# CustomPower.net
KiCad netlist of a schematic drawn in EAGLE
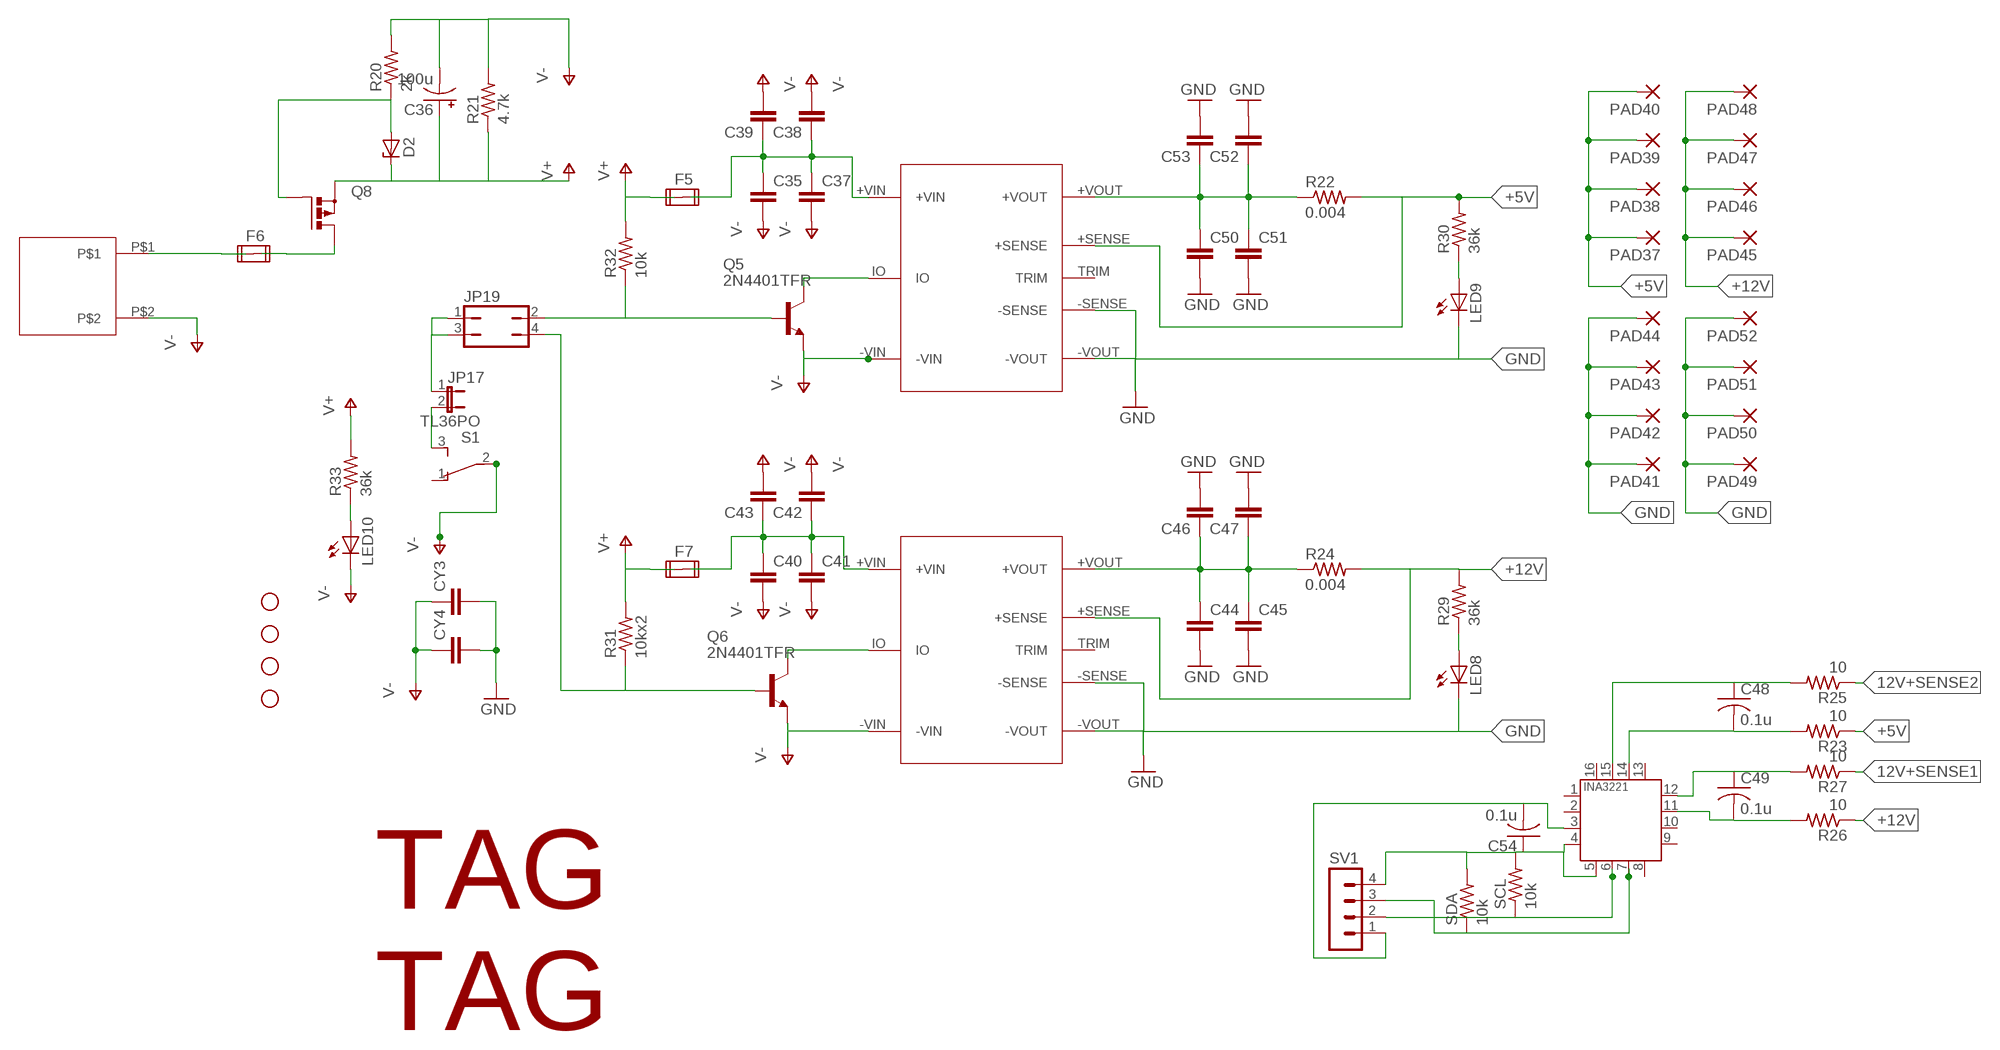
[diagram p0: schematic, sheet 1]

(export (version "E")
  (design (tool "Eeschema 10.0.6"))
  (components
    (comp (ref "C35")
      (value "C-EU050-035X075")
      (footprint "eagle-import:C050-035X075")
      (libsource (lib "eagle-import") (part "C-EU050-035X075"))
    )
    (comp (ref "C36")
      (value "100u")
      (footprint "eagle-import:E3,5-8")
      (libsource (lib "eagle-import") (part "CPOL-USE3.5-8"))
    )
    (comp (ref "C37")
      (value "C-EU050-035X075")
      (footprint "eagle-import:C050-035X075")
      (libsource (lib "eagle-import") (part "C-EU050-035X075"))
    )
    (comp (ref "C38")
      (value "C-EU050-035X075")
      (footprint "eagle-import:C050-035X075")
      (libsource (lib "eagle-import") (part "C-EU050-035X075"))
    )
    (comp (ref "C39")
      (value "C-EU050-035X075")
      (footprint "eagle-import:C050-035X075")
      (libsource (lib "eagle-import") (part "C-EU050-035X075"))
    )
    (comp (ref "C40")
      (value "C-EU050-035X075")
      (footprint "eagle-import:C050-035X075")
      (libsource (lib "eagle-import") (part "C-EU050-035X075"))
    )
    (comp (ref "C41")
      (value "C-EU050-035X075")
      (footprint "eagle-import:C050-035X075")
      (libsource (lib "eagle-import") (part "C-EU050-035X075"))
    )
    (comp (ref "C42")
      (value "C-EU050-035X075")
      (footprint "eagle-import:C050-035X075")
      (libsource (lib "eagle-import") (part "C-EU050-035X075"))
    )
    (comp (ref "C43")
      (value "C-EU050-035X075")
      (footprint "eagle-import:C050-035X075")
      (libsource (lib "eagle-import") (part "C-EU050-035X075"))
    )
    (comp (ref "C44")
      (value "C-EU025-040X050")
      (footprint "eagle-import:C025-040X050")
      (libsource (lib "eagle-import") (part "C-EU025-040X050"))
    )
    (comp (ref "C45")
      (value "C-EU025-040X050")
      (footprint "eagle-import:C025-040X050")
      (libsource (lib "eagle-import") (part "C-EU025-040X050"))
    )
    (comp (ref "C46")
      (value "C-EU025-040X050")
      (footprint "eagle-import:C025-040X050")
      (libsource (lib "eagle-import") (part "C-EU025-040X050"))
    )
    (comp (ref "C47")
      (value "C-EU025-040X050")
      (footprint "eagle-import:C025-040X050")
      (libsource (lib "eagle-import") (part "C-EU025-040X050"))
    )
    (comp (ref "C48")
      (value "0.1u")
      (footprint "eagle-import:C0805K")
      (libsource (lib "eagle-import") (part "C-USC0805K"))
    )
    (comp (ref "C49")
      (value "0.1u")
      (footprint "eagle-import:C0805K")
      (libsource (lib "eagle-import") (part "C-USC0805K"))
    )
    (comp (ref "C50")
      (value "C-EU025-040X050")
      (footprint "eagle-import:C025-040X050")
      (libsource (lib "eagle-import") (part "C-EU025-040X050"))
    )
    (comp (ref "C51")
      (value "C-EU025-040X050")
      (footprint "eagle-import:C025-040X050")
      (libsource (lib "eagle-import") (part "C-EU025-040X050"))
    )
    (comp (ref "C52")
      (value "C-EU025-040X050")
      (footprint "eagle-import:C025-040X050")
      (libsource (lib "eagle-import") (part "C-EU025-040X050"))
    )
    (comp (ref "C53")
      (value "C-EU025-040X050")
      (footprint "eagle-import:C025-040X050")
      (libsource (lib "eagle-import") (part "C-EU025-040X050"))
    )
    (comp (ref "C54")
      (value "0.1u")
      (footprint "eagle-import:C0805K")
      (libsource (lib "eagle-import") (part "C-USC0805K"))
    )
    (comp (ref "CY3")
      (value "CYYC7B5")
      (footprint "eagle-import:YC7B5")
      (libsource (lib "eagle-import") (part "CYYC7B5"))
    )
    (comp (ref "CY4")
      (value "CYYC7B5")
      (footprint "eagle-import:YC7B5")
      (libsource (lib "eagle-import") (part "CYYC7B5"))
    )
    (comp (ref "D2")
      (value "BZV10")
      (footprint "eagle-import:DO34Z7")
      (libsource (lib "eagle-import") (part "BZV10"))
    )
    (comp (ref "F5")
      (value "FUSE2P")
      (footprint "eagle-import:FUSE1")
      (libsource (lib "eagle-import") (part "FUSE2P"))
    )
    (comp (ref "F6")
      (value "FUSE2P")
      (footprint "eagle-import:FUSE1")
      (fields (field (name "SPICEPREFIX") "E"))
      (libsource (lib "eagle-import") (part "FUSE2P"))
    )
    (comp (ref "F7")
      (value "FUSE2P")
      (footprint "eagle-import:FUSE1")
      (libsource (lib "eagle-import") (part "FUSE2P"))
    )
    (comp (ref "JP3")
      (value "STAND-OFF")
      (footprint "eagle-import:STAND-OFF")
      (libsource (lib "eagle-import") (part "STAND-OFF"))
    )
    (comp (ref "JP4")
      (value "STAND-OFF")
      (footprint "eagle-import:STAND-OFF")
      (libsource (lib "eagle-import") (part "STAND-OFF"))
    )
    (comp (ref "JP5")
      (value "STAND-OFF")
      (footprint "eagle-import:STAND-OFF")
      (libsource (lib "eagle-import") (part "STAND-OFF"))
    )
    (comp (ref "JP6")
      (value "STAND-OFF")
      (footprint "eagle-import:STAND-OFF")
      (libsource (lib "eagle-import") (part "STAND-OFF"))
    )
    (comp (ref "JP17")
      (value "JP1E")
      (footprint "eagle-import:JP1")
      (libsource (lib "eagle-import") (part "JP1E"))
    )
    (comp (ref "JP19")
      (value "JP2Q")
      (footprint "eagle-import:JP2Q")
      (libsource (lib "eagle-import") (part "JP2Q"))
    )
    (comp (ref "LED8")
      (value "LEDSMT1206")
      (footprint "eagle-import:1206")
      (libsource (lib "eagle-import") (part "LEDSMT1206"))
    )
    (comp (ref "LED9")
      (value "LEDSMT1206")
      (footprint "eagle-import:1206")
      (libsource (lib "eagle-import") (part "LEDSMT1206"))
    )
    (comp (ref "LED10")
      (value "LEDSMT1206")
      (footprint "eagle-import:1206")
      (libsource (lib "eagle-import") (part "LEDSMT1206"))
    )
    (comp (ref "PAD37")
      (value "WIREPAD3,17/1,3")
      (footprint "eagle-import:3,17_1,3")
      (libsource (lib "eagle-import") (part "WIREPAD3,17/1,3"))
    )
    (comp (ref "PAD38")
      (value "WIREPAD3,17/1,3")
      (footprint "eagle-import:3,17_1,3")
      (libsource (lib "eagle-import") (part "WIREPAD3,17/1,3"))
    )
    (comp (ref "PAD39")
      (value "WIREPAD3,17/1,3")
      (footprint "eagle-import:3,17_1,3")
      (libsource (lib "eagle-import") (part "WIREPAD3,17/1,3"))
    )
    (comp (ref "PAD40")
      (value "WIREPAD3,17/1,3")
      (footprint "eagle-import:3,17_1,3")
      (libsource (lib "eagle-import") (part "WIREPAD3,17/1,3"))
    )
    (comp (ref "PAD41")
      (value "WIREPAD3,17/1,3")
      (footprint "eagle-import:3,17_1,3")
      (libsource (lib "eagle-import") (part "WIREPAD3,17/1,3"))
    )
    (comp (ref "PAD42")
      (value "WIREPAD3,17/1,3")
      (footprint "eagle-import:3,17_1,3")
      (libsource (lib "eagle-import") (part "WIREPAD3,17/1,3"))
    )
    (comp (ref "PAD43")
      (value "WIREPAD3,17/1,3")
      (footprint "eagle-import:3,17_1,3")
      (libsource (lib "eagle-import") (part "WIREPAD3,17/1,3"))
    )
    (comp (ref "PAD44")
      (value "WIREPAD3,17/1,3")
      (footprint "eagle-import:3,17_1,3")
      (libsource (lib "eagle-import") (part "WIREPAD3,17/1,3"))
    )
    (comp (ref "PAD45")
      (value "WIREPAD3,17/1,3")
      (footprint "eagle-import:3,17_1,3")
      (libsource (lib "eagle-import") (part "WIREPAD3,17/1,3"))
    )
    (comp (ref "PAD46")
      (value "WIREPAD3,17/1,3")
      (footprint "eagle-import:3,17_1,3")
      (libsource (lib "eagle-import") (part "WIREPAD3,17/1,3"))
    )
    (comp (ref "PAD47")
      (value "WIREPAD3,17/1,3")
      (footprint "eagle-import:3,17_1,3")
      (libsource (lib "eagle-import") (part "WIREPAD3,17/1,3"))
    )
    (comp (ref "PAD48")
      (value "WIREPAD3,17/1,3")
      (footprint "eagle-import:3,17_1,3")
      (libsource (lib "eagle-import") (part "WIREPAD3,17/1,3"))
    )
    (comp (ref "PAD49")
      (value "WIREPAD3,17/1,3")
      (footprint "eagle-import:3,17_1,3")
      (libsource (lib "eagle-import") (part "WIREPAD3,17/1,3"))
    )
    (comp (ref "PAD50")
      (value "WIREPAD3,17/1,3")
      (footprint "eagle-import:3,17_1,3")
      (libsource (lib "eagle-import") (part "WIREPAD3,17/1,3"))
    )
    (comp (ref "PAD51")
      (value "WIREPAD3,17/1,3")
      (footprint "eagle-import:3,17_1,3")
      (libsource (lib "eagle-import") (part "WIREPAD3,17/1,3"))
    )
    (comp (ref "PAD52")
      (value "WIREPAD3,17/1,3")
      (footprint "eagle-import:3,17_1,3")
      (libsource (lib "eagle-import") (part "WIREPAD3,17/1,3"))
    )
    (comp (ref "Q5")
      (value "2N4401TFR")
      (footprint "eagle-import:TO92-EBC")
      (libsource (lib "eagle-import") (part "2N4401TFR"))
    )
    (comp (ref "Q6")
      (value "2N4401TFR")
      (footprint "eagle-import:TO92-EBC")
      (libsource (lib "eagle-import") (part "2N4401TFR"))
    )
    (comp (ref "Q8")
      (value "PMOSFET_PTO220BV")
      (footprint "eagle-import:TO220BV")
      (libsource (lib "eagle-import") (part "PMOSFET_PTO220BV"))
    )
    (comp (ref "R20")
      (value "2k")
      (footprint "eagle-import:0204_7")
      (libsource (lib "eagle-import") (part "resistor_348_R-US_0204/7"))
    )
    (comp (ref "R21")
      (value "4.7k")
      (footprint "eagle-import:0204_7")
      (libsource (lib "eagle-import") (part "resistor_348_R-US_0204/7"))
    )
    (comp (ref "R22")
      (value "0.004")
      (footprint "eagle-import:0617_22")
      (libsource (lib "eagle-import") (part "R-US_0617/22"))
    )
    (comp (ref "R23")
      (value "10")
      (footprint "eagle-import:R0805")
      (libsource (lib "eagle-import") (part "resistor_348_R-US_R0805"))
    )
    (comp (ref "R24")
      (value "0.004")
      (footprint "eagle-import:0617_22")
      (libsource (lib "eagle-import") (part "R-US_0617/22"))
    )
    (comp (ref "R25")
      (value "10")
      (footprint "eagle-import:R0805")
      (libsource (lib "eagle-import") (part "resistor_348_R-US_R0805"))
    )
    (comp (ref "R26")
      (value "10")
      (footprint "eagle-import:R0805")
      (libsource (lib "eagle-import") (part "resistor_348_R-US_R0805"))
    )
    (comp (ref "R27")
      (value "10")
      (footprint "eagle-import:R0805")
      (libsource (lib "eagle-import") (part "resistor_348_R-US_R0805"))
    )
    (comp (ref "R29")
      (value "36k")
      (footprint "eagle-import:R0805")
      (libsource (lib "eagle-import") (part "resistor_348_R-US_R0805"))
    )
    (comp (ref "R30")
      (value "36k")
      (footprint "eagle-import:R0805")
      (libsource (lib "eagle-import") (part "resistor_348_R-US_R0805"))
    )
    (comp (ref "R31")
      (value "10kx2")
      (footprint "eagle-import:R0805")
      (libsource (lib "eagle-import") (part "resistor_348_R-US_R0805"))
    )
    (comp (ref "R32")
      (value "10k")
      (footprint "eagle-import:R0805")
      (libsource (lib "eagle-import") (part "resistor_348_R-US_R0805"))
    )
    (comp (ref "R33")
      (value "36k")
      (footprint "eagle-import:R0805")
      (libsource (lib "eagle-import") (part "resistor_348_R-US_R0805"))
    )
    (comp (ref "S1")
      (value "TL36PO")
      (footprint "eagle-import:TL3XPO")
      (libsource (lib "eagle-import") (part "TL36PO"))
    )
    (comp (ref "SCL")
      (value "10k")
      (footprint "eagle-import:R0805")
      (libsource (lib "eagle-import") (part "resistor_348_R-US_R0805"))
    )
    (comp (ref "SDA")
      (value "10k")
      (footprint "eagle-import:R0805")
      (libsource (lib "eagle-import") (part "resistor_348_R-US_R0805"))
    )
    (comp (ref "SV1")
      (value "MA04-1")
      (footprint "eagle-import:MA04-1")
      (libsource (lib "eagle-import") (part "MA04-1"))
    )
    (comp (ref "U$1")
      (value "MURATA_BRICK")
      (footprint "eagle-import:MURATA_BRICK")
      (libsource (lib "eagle-import") (part "MURATA_BRICK"))
    )
    (comp (ref "U$2")
      (value "MURATA_BRICK")
      (footprint "eagle-import:MURATA_BRICK")
      (libsource (lib "eagle-import") (part "MURATA_BRICK"))
    )
    (comp (ref "U$3")
      (value "TERM_POWER")
      (footprint "eagle-import:TERM_BLOCK_POWER")
      (libsource (lib "eagle-import") (part "TERM_POWER"))
    )
    (comp (ref "U$4")
      (value "TAG")
      (footprint "eagle-import:TAG")
      (libsource (lib "eagle-import") (part "TAG"))
    )
    (comp (ref "U$5")
      (value "TAG")
      (footprint "eagle-import:TAG")
      (libsource (lib "eagle-import") (part "TAG"))
    )
    (comp (ref "U3")
      (value "INA3221.")
      (footprint "eagle-import:HVQFN16_4X4")
      (libsource (lib "eagle-import") (part "INA3221."))
    )
  )
  (nets
    (net (code "1") (name "+5V") (class "Default")
      (node (ref "PAD37") (pin "1") (pinfunction "P_1") (pintype "passive"))
      (node (ref "PAD38") (pin "1") (pinfunction "P_1") (pintype "passive"))
      (node (ref "PAD39") (pin "1") (pinfunction "P_1") (pintype "passive"))
      (node (ref "PAD40") (pin "1") (pinfunction "P_1") (pintype "passive"))
      (node (ref "R22") (pin "2") (pinfunction "2_2") (pintype "passive"))
      (node (ref "R23") (pin "1") (pinfunction "1_1") (pintype "passive"))
      (node (ref "R30") (pin "2") (pinfunction "2_2") (pintype "passive"))
      (node (ref "U$1") (pin "+SENSE") (pinfunction "+SENSE_+SENSE") (pintype "bidirectional"))
    )
    (net (code "2") (name "+12V") (class "Default")
      (node (ref "PAD45") (pin "1") (pinfunction "P_1") (pintype "passive"))
      (node (ref "PAD46") (pin "1") (pinfunction "P_1") (pintype "passive"))
      (node (ref "PAD47") (pin "1") (pinfunction "P_1") (pintype "passive"))
      (node (ref "PAD48") (pin "1") (pinfunction "P_1") (pintype "passive"))
      (node (ref "R24") (pin "2") (pinfunction "2_2") (pintype "passive"))
      (node (ref "R26") (pin "1") (pinfunction "1_1") (pintype "passive"))
      (node (ref "R29") (pin "2") (pinfunction "2_2") (pintype "passive"))
      (node (ref "U$2") (pin "+SENSE") (pinfunction "+SENSE_+SENSE") (pintype "bidirectional"))
    )
    (net (code "3") (name "12V+SENSE1") (class "Default")
      (node (ref "C44") (pin "1") (pinfunction "1_1") (pintype "passive"))
      (node (ref "C45") (pin "1") (pinfunction "1_1") (pintype "passive"))
      (node (ref "C46") (pin "1") (pinfunction "1_1") (pintype "passive"))
      (node (ref "C47") (pin "1") (pinfunction "1_1") (pintype "passive"))
      (node (ref "R24") (pin "1") (pinfunction "1_1") (pintype "passive"))
      (node (ref "R27") (pin "1") (pinfunction "1_1") (pintype "passive"))
      (node (ref "U$2") (pin "+VOUT") (pinfunction "+VOUT_+VOUT") (pintype "bidirectional"))
    )
    (net (code "4") (name "12V+SENSE2") (class "Default")
      (node (ref "C50") (pin "1") (pinfunction "1_1") (pintype "passive"))
      (node (ref "C51") (pin "1") (pinfunction "1_1") (pintype "passive"))
      (node (ref "C52") (pin "1") (pinfunction "1_1") (pintype "passive"))
      (node (ref "C53") (pin "1") (pinfunction "1_1") (pintype "passive"))
      (node (ref "R22") (pin "1") (pinfunction "1_1") (pintype "passive"))
      (node (ref "R25") (pin "1") (pinfunction "1_1") (pintype "passive"))
      (node (ref "U$1") (pin "+VOUT") (pinfunction "+VOUT_+VOUT") (pintype "bidirectional"))
    )
    (net (code "5") (name "GND") (class "Default")
      (node (ref "C44") (pin "2") (pinfunction "2_2") (pintype "passive"))
      (node (ref "C45") (pin "2") (pinfunction "2_2") (pintype "passive"))
      (node (ref "C46") (pin "2") (pinfunction "2_2") (pintype "passive"))
      (node (ref "C47") (pin "2") (pinfunction "2_2") (pintype "passive"))
      (node (ref "C50") (pin "2") (pinfunction "2_2") (pintype "passive"))
      (node (ref "C51") (pin "2") (pinfunction "2_2") (pintype "passive"))
      (node (ref "C52") (pin "2") (pinfunction "2_2") (pintype "passive"))
      (node (ref "C53") (pin "2") (pinfunction "2_2") (pintype "passive"))
      (node (ref "CY3") (pin "2") (pinfunction "2_2") (pintype "passive"))
      (node (ref "CY4") (pin "2") (pinfunction "2_2") (pintype "passive"))
      (node (ref "LED8") (pin "C") (pinfunction "C_C") (pintype "passive"))
      (node (ref "LED9") (pin "C") (pinfunction "C_C") (pintype "passive"))
      (node (ref "PAD41") (pin "1") (pinfunction "P_1") (pintype "passive"))
      (node (ref "PAD42") (pin "1") (pinfunction "P_1") (pintype "passive"))
      (node (ref "PAD43") (pin "1") (pinfunction "P_1") (pintype "passive"))
      (node (ref "PAD44") (pin "1") (pinfunction "P_1") (pintype "passive"))
      (node (ref "PAD49") (pin "1") (pinfunction "P_1") (pintype "passive"))
      (node (ref "PAD50") (pin "1") (pinfunction "P_1") (pintype "passive"))
      (node (ref "PAD51") (pin "1") (pinfunction "P_1") (pintype "passive"))
      (node (ref "PAD52") (pin "1") (pinfunction "P_1") (pintype "passive"))
      (node (ref "U$1") (pin "-SENSE") (pinfunction "-SENSE_-SENSE") (pintype "bidirectional"))
      (node (ref "U$1") (pin "-VOUT") (pinfunction "-VOUT_-VOUT") (pintype "bidirectional"))
      (node (ref "U$2") (pin "-SENSE") (pinfunction "-SENSE_-SENSE") (pintype "bidirectional"))
      (node (ref "U$2") (pin "-VOUT") (pinfunction "-VOUT_-VOUT") (pintype "bidirectional"))
    )
    (net (code "6") (name "Net-(C35-Pad1)") (class "Default")
      (node (ref "C35") (pin "1") (pinfunction "1_1") (pintype "passive"))
      (node (ref "C37") (pin "1") (pinfunction "1_1") (pintype "passive"))
      (node (ref "C38") (pin "1") (pinfunction "1_1") (pintype "passive"))
      (node (ref "C39") (pin "1") (pinfunction "1_1") (pintype "passive"))
      (node (ref "F5") (pin "2A") (pinfunction "2A_2A") (pintype "passive"))
      (node (ref "F5") (pin "2B") (pinfunction "2B_2B") (pintype "passive"))
      (node (ref "U$1") (pin "+VIN") (pinfunction "+VIN_+VIN") (pintype "bidirectional"))
    )
    (net (code "7") (name "Net-(C40-Pad1)") (class "Default")
      (node (ref "C40") (pin "1") (pinfunction "1_1") (pintype "passive"))
      (node (ref "C41") (pin "1") (pinfunction "1_1") (pintype "passive"))
      (node (ref "C42") (pin "1") (pinfunction "1_1") (pintype "passive"))
      (node (ref "C43") (pin "1") (pinfunction "1_1") (pintype "passive"))
      (node (ref "F7") (pin "2A") (pinfunction "2A_2A") (pintype "passive"))
      (node (ref "F7") (pin "2B") (pinfunction "2B_2B") (pintype "passive"))
      (node (ref "U$2") (pin "+VIN") (pinfunction "+VIN_+VIN") (pintype "bidirectional"))
    )
    (net (code "8") (name "Net-(D2-PadA)") (class "Default")
      (node (ref "D2") (pin "A") (pinfunction "A_A") (pintype "passive"))
      (node (ref "Q8") (pin "G") (pinfunction "G_G") (pintype "passive"))
      (node (ref "R20") (pin "1") (pinfunction "1_1") (pintype "passive"))
    )
    (net (code "9") (name "Net-(F6-Pad1A)") (class "Default")
      (node (ref "F6") (pin "1A") (pinfunction "1A_1A") (pintype "passive"))
      (node (ref "F6") (pin "1B") (pinfunction "1B_1B") (pintype "passive"))
      (node (ref "U$3") (pin "P$1") (pinfunction "P$1_P$1") (pintype "bidirectional"))
    )
    (net (code "10") (name "Net-(F6-Pad2A)") (class "Default")
      (node (ref "F6") (pin "2A") (pinfunction "2A_2A") (pintype "passive"))
      (node (ref "F6") (pin "2B") (pinfunction "2B_2B") (pintype "passive"))
      (node (ref "Q8") (pin "D") (pinfunction "D_D") (pintype "passive"))
    )
    (net (code "11") (name "Net-(JP17-Pad1)") (class "Default")
      (node (ref "JP17") (pin "1") (pinfunction "1_1") (pintype "passive"))
      (node (ref "JP19") (pin "1") (pinfunction "1_1") (pintype "passive"))
      (node (ref "JP19") (pin "3") (pinfunction "3_3") (pintype "passive"))
    )
    (net (code "12") (name "Net-(JP19-Pad2)") (class "Default")
      (node (ref "JP19") (pin "2") (pinfunction "2_2") (pintype "passive"))
      (node (ref "Q5") (pin "B") (pinfunction "B_B") (pintype "passive"))
      (node (ref "R32") (pin "1") (pinfunction "1_1") (pintype "passive"))
    )
    (net (code "13") (name "Net-(JP19-Pad4)") (class "Default")
      (node (ref "JP19") (pin "4") (pinfunction "4_4") (pintype "passive"))
      (node (ref "Q6") (pin "B") (pinfunction "B_B") (pintype "passive"))
      (node (ref "R31") (pin "1") (pinfunction "1_1") (pintype "passive"))
    )
    (net (code "14") (name "Net-(LED8-PadA)") (class "Default")
      (node (ref "LED8") (pin "A") (pinfunction "A_A") (pintype "passive"))
      (node (ref "R29") (pin "1") (pinfunction "1_1") (pintype "passive"))
    )
    (net (code "15") (name "Net-(LED9-PadA)") (class "Default")
      (node (ref "LED9") (pin "A") (pinfunction "A_A") (pintype "passive"))
      (node (ref "R30") (pin "1") (pinfunction "1_1") (pintype "passive"))
    )
    (net (code "16") (name "Net-(LED10-PadA)") (class "Default")
      (node (ref "LED10") (pin "A") (pinfunction "A_A") (pintype "passive"))
      (node (ref "R33") (pin "1") (pinfunction "1_1") (pintype "passive"))
    )
    (net (code "17") (name "Net-(Q5-PadC)") (class "Default")
      (node (ref "Q5") (pin "C") (pinfunction "C_C") (pintype "passive"))
      (node (ref "U$1") (pin "IO") (pinfunction "IO_IO") (pintype "bidirectional"))
    )
    (net (code "18") (name "Net-(Q6-PadC)") (class "Default")
      (node (ref "Q6") (pin "C") (pinfunction "C_C") (pintype "passive"))
      (node (ref "U$2") (pin "IO") (pinfunction "IO_IO") (pintype "bidirectional"))
    )
    (net (code "19") (name "Net-(S1-S)") (class "Default")
      (node (ref "JP17") (pin "2") (pinfunction "2_2") (pintype "passive"))
      (node (ref "S1") (pin "3") (pinfunction "S_3") (pintype "passive"))
    )
    (net (code "20") (name "Net-(U3-A0)") (class "Default")
      (node (ref "C54") (pin "1") (pinfunction "1_1") (pintype "passive"))
      (node (ref "SCL") (pin "2") (pinfunction "2_2") (pintype "passive"))
      (node (ref "SDA") (pin "2") (pinfunction "2_2") (pintype "passive"))
      (node (ref "SV1") (pin "4") (pinfunction "4_4") (pintype "passive"))
      (node (ref "U3") (pin "4") (pinfunction "VS_4") (pintype "power_in"))
      (node (ref "U3") (pin "5") (pinfunction "A0_5") (pintype "input"))
    )
    (net (code "21") (name "Net-(U3-GND)") (class "Default")
      (node (ref "C54") (pin "2") (pinfunction "2_2") (pintype "passive"))
      (node (ref "SV1") (pin "1") (pinfunction "1_1") (pintype "passive"))
      (node (ref "U3") (pin "3") (pinfunction "GND_3") (pintype "power_in"))
    )
    (net (code "22") (name "Net-(U3-IN+1)") (class "Default")
      (node (ref "C49") (pin "1") (pinfunction "1_1") (pintype "passive"))
      (node (ref "R27") (pin "2") (pinfunction "2_2") (pintype "passive"))
      (node (ref "U3") (pin "12") (pinfunction "IN+1_12") (pintype "input"))
    )
    (net (code "23") (name "Net-(U3-IN+2)") (class "Default")
      (node (ref "C48") (pin "1") (pinfunction "1_1") (pintype "passive"))
      (node (ref "R25") (pin "2") (pinfunction "2_2") (pintype "passive"))
      (node (ref "U3") (pin "15") (pinfunction "IN+2_15") (pintype "input"))
    )
    (net (code "24") (name "Net-(U3-IN-1)") (class "Default")
      (node (ref "C49") (pin "2") (pinfunction "2_2") (pintype "passive"))
      (node (ref "R26") (pin "2") (pinfunction "2_2") (pintype "passive"))
      (node (ref "U3") (pin "11") (pinfunction "IN-1_11") (pintype "input"))
    )
    (net (code "25") (name "Net-(U3-IN-2)") (class "Default")
      (node (ref "C48") (pin "2") (pinfunction "2_2") (pintype "passive"))
      (node (ref "R23") (pin "2") (pinfunction "2_2") (pintype "passive"))
      (node (ref "U3") (pin "14") (pinfunction "IN-2_14") (pintype "input"))
    )
    (net (code "26") (name "Net-(U3-SCL)") (class "Default")
      (node (ref "SCL") (pin "1") (pinfunction "1_1") (pintype "passive"))
      (node (ref "SV1") (pin "2") (pinfunction "2_2") (pintype "passive"))
      (node (ref "U3") (pin "6") (pinfunction "SCL_6") (pintype "input"))
    )
    (net (code "27") (name "Net-(U3-SDA)") (class "Default")
      (node (ref "SDA") (pin "1") (pinfunction "1_1") (pintype "passive"))
      (node (ref "SV1") (pin "3") (pinfunction "3_3") (pintype "passive"))
      (node (ref "U3") (pin "7") (pinfunction "SDA_7") (pintype "bidirectional"))
    )
    (net (code "28") (name "V+") (class "Default")
      (node (ref "C36") (pin "+") (pinfunction "+_+") (pintype "passive"))
      (node (ref "D2") (pin "C") (pinfunction "C_C") (pintype "passive"))
      (node (ref "F5") (pin "1A") (pinfunction "1A_1A") (pintype "passive"))
      (node (ref "F5") (pin "1B") (pinfunction "1B_1B") (pintype "passive"))
      (node (ref "F7") (pin "1A") (pinfunction "1A_1A") (pintype "passive"))
      (node (ref "F7") (pin "1B") (pinfunction "1B_1B") (pintype "passive"))
      (node (ref "Q8") (pin "S") (pinfunction "S_S") (pintype "passive"))
      (node (ref "R21") (pin "1") (pinfunction "1_1") (pintype "passive"))
      (node (ref "R31") (pin "2") (pinfunction "2_2") (pintype "passive"))
      (node (ref "R32") (pin "2") (pinfunction "2_2") (pintype "passive"))
      (node (ref "R33") (pin "2") (pinfunction "2_2") (pintype "passive"))
    )
    (net (code "29") (name "V-") (class "Default")
      (node (ref "C35") (pin "2") (pinfunction "2_2") (pintype "passive"))
      (node (ref "C36") (pin "-") (pinfunction "-_-") (pintype "passive"))
      (node (ref "C37") (pin "2") (pinfunction "2_2") (pintype "passive"))
      (node (ref "C38") (pin "2") (pinfunction "2_2") (pintype "passive"))
      (node (ref "C39") (pin "2") (pinfunction "2_2") (pintype "passive"))
      (node (ref "C40") (pin "2") (pinfunction "2_2") (pintype "passive"))
      (node (ref "C41") (pin "2") (pinfunction "2_2") (pintype "passive"))
      (node (ref "C42") (pin "2") (pinfunction "2_2") (pintype "passive"))
      (node (ref "C43") (pin "2") (pinfunction "2_2") (pintype "passive"))
      (node (ref "CY3") (pin "1") (pinfunction "1_1") (pintype "passive"))
      (node (ref "CY4") (pin "1") (pinfunction "1_1") (pintype "passive"))
      (node (ref "LED10") (pin "C") (pinfunction "C_C") (pintype "passive"))
      (node (ref "Q5") (pin "E") (pinfunction "E_E") (pintype "passive"))
      (node (ref "Q6") (pin "E") (pinfunction "E_E") (pintype "passive"))
      (node (ref "R20") (pin "2") (pinfunction "2_2") (pintype "passive"))
      (node (ref "R21") (pin "2") (pinfunction "2_2") (pintype "passive"))
      (node (ref "S1") (pin "2") (pinfunction "P_2") (pintype "passive"))
      (node (ref "U$1") (pin "-VIN") (pinfunction "-VIN_-VIN") (pintype "bidirectional"))
      (node (ref "U$2") (pin "-VIN") (pinfunction "-VIN_-VIN") (pintype "bidirectional"))
      (node (ref "U$3") (pin "P$2") (pinfunction "P$2_P$2") (pintype "bidirectional"))
    )
    (net (code "30") (name "unconnected-(S1-O-Pad1)") (class "Default")
      (node (ref "S1") (pin "1") (pinfunction "O_1") (pintype "passive"))
    )
    (net (code "31") (name "unconnected-(U$1-PadTRIM)") (class "Default")
      (node (ref "U$1") (pin "TRIM") (pinfunction "TRIM_TRIM") (pintype "bidirectional"))
    )
    (net (code "32") (name "unconnected-(U$2-PadTRIM)") (class "Default")
      (node (ref "U$2") (pin "TRIM") (pinfunction "TRIM_TRIM") (pintype "bidirectional"))
    )
    (net (code "33") (name "unconnected-(U3-CRITICAL-Pad9)") (class "Default")
      (node (ref "U3") (pin "9") (pinfunction "CRITICAL_9") (pintype "output"))
    )
    (net (code "34") (name "unconnected-(U3-IN+3-Pad2)") (class "Default")
      (node (ref "U3") (pin "2") (pinfunction "IN+3_2") (pintype "input"))
    )
    (net (code "35") (name "unconnected-(U3-IN-3-Pad1)") (class "Default")
      (node (ref "U3") (pin "1") (pinfunction "IN-3_1") (pintype "input"))
    )
    (net (code "36") (name "unconnected-(U3-PV-Pad10)") (class "Default")
      (node (ref "U3") (pin "10") (pinfunction "PV_10") (pintype "output"))
    )
    (net (code "37") (name "unconnected-(U3-TC-Pad13)") (class "Default")
      (node (ref "U3") (pin "13") (pinfunction "TC_13") (pintype "output"))
    )
    (net (code "38") (name "unconnected-(U3-VPU-Pad16)") (class "Default")
      (node (ref "U3") (pin "16") (pinfunction "VPU_16") (pintype "input"))
    )
    (net (code "39") (name "unconnected-(U3-WARNING-Pad8)") (class "Default")
      (node (ref "U3") (pin "8") (pinfunction "WARNING_8") (pintype "output"))
    )
  )
)
